# love_compass.net
KiCad netlist of a schematic drawn in EasyEDA Pro
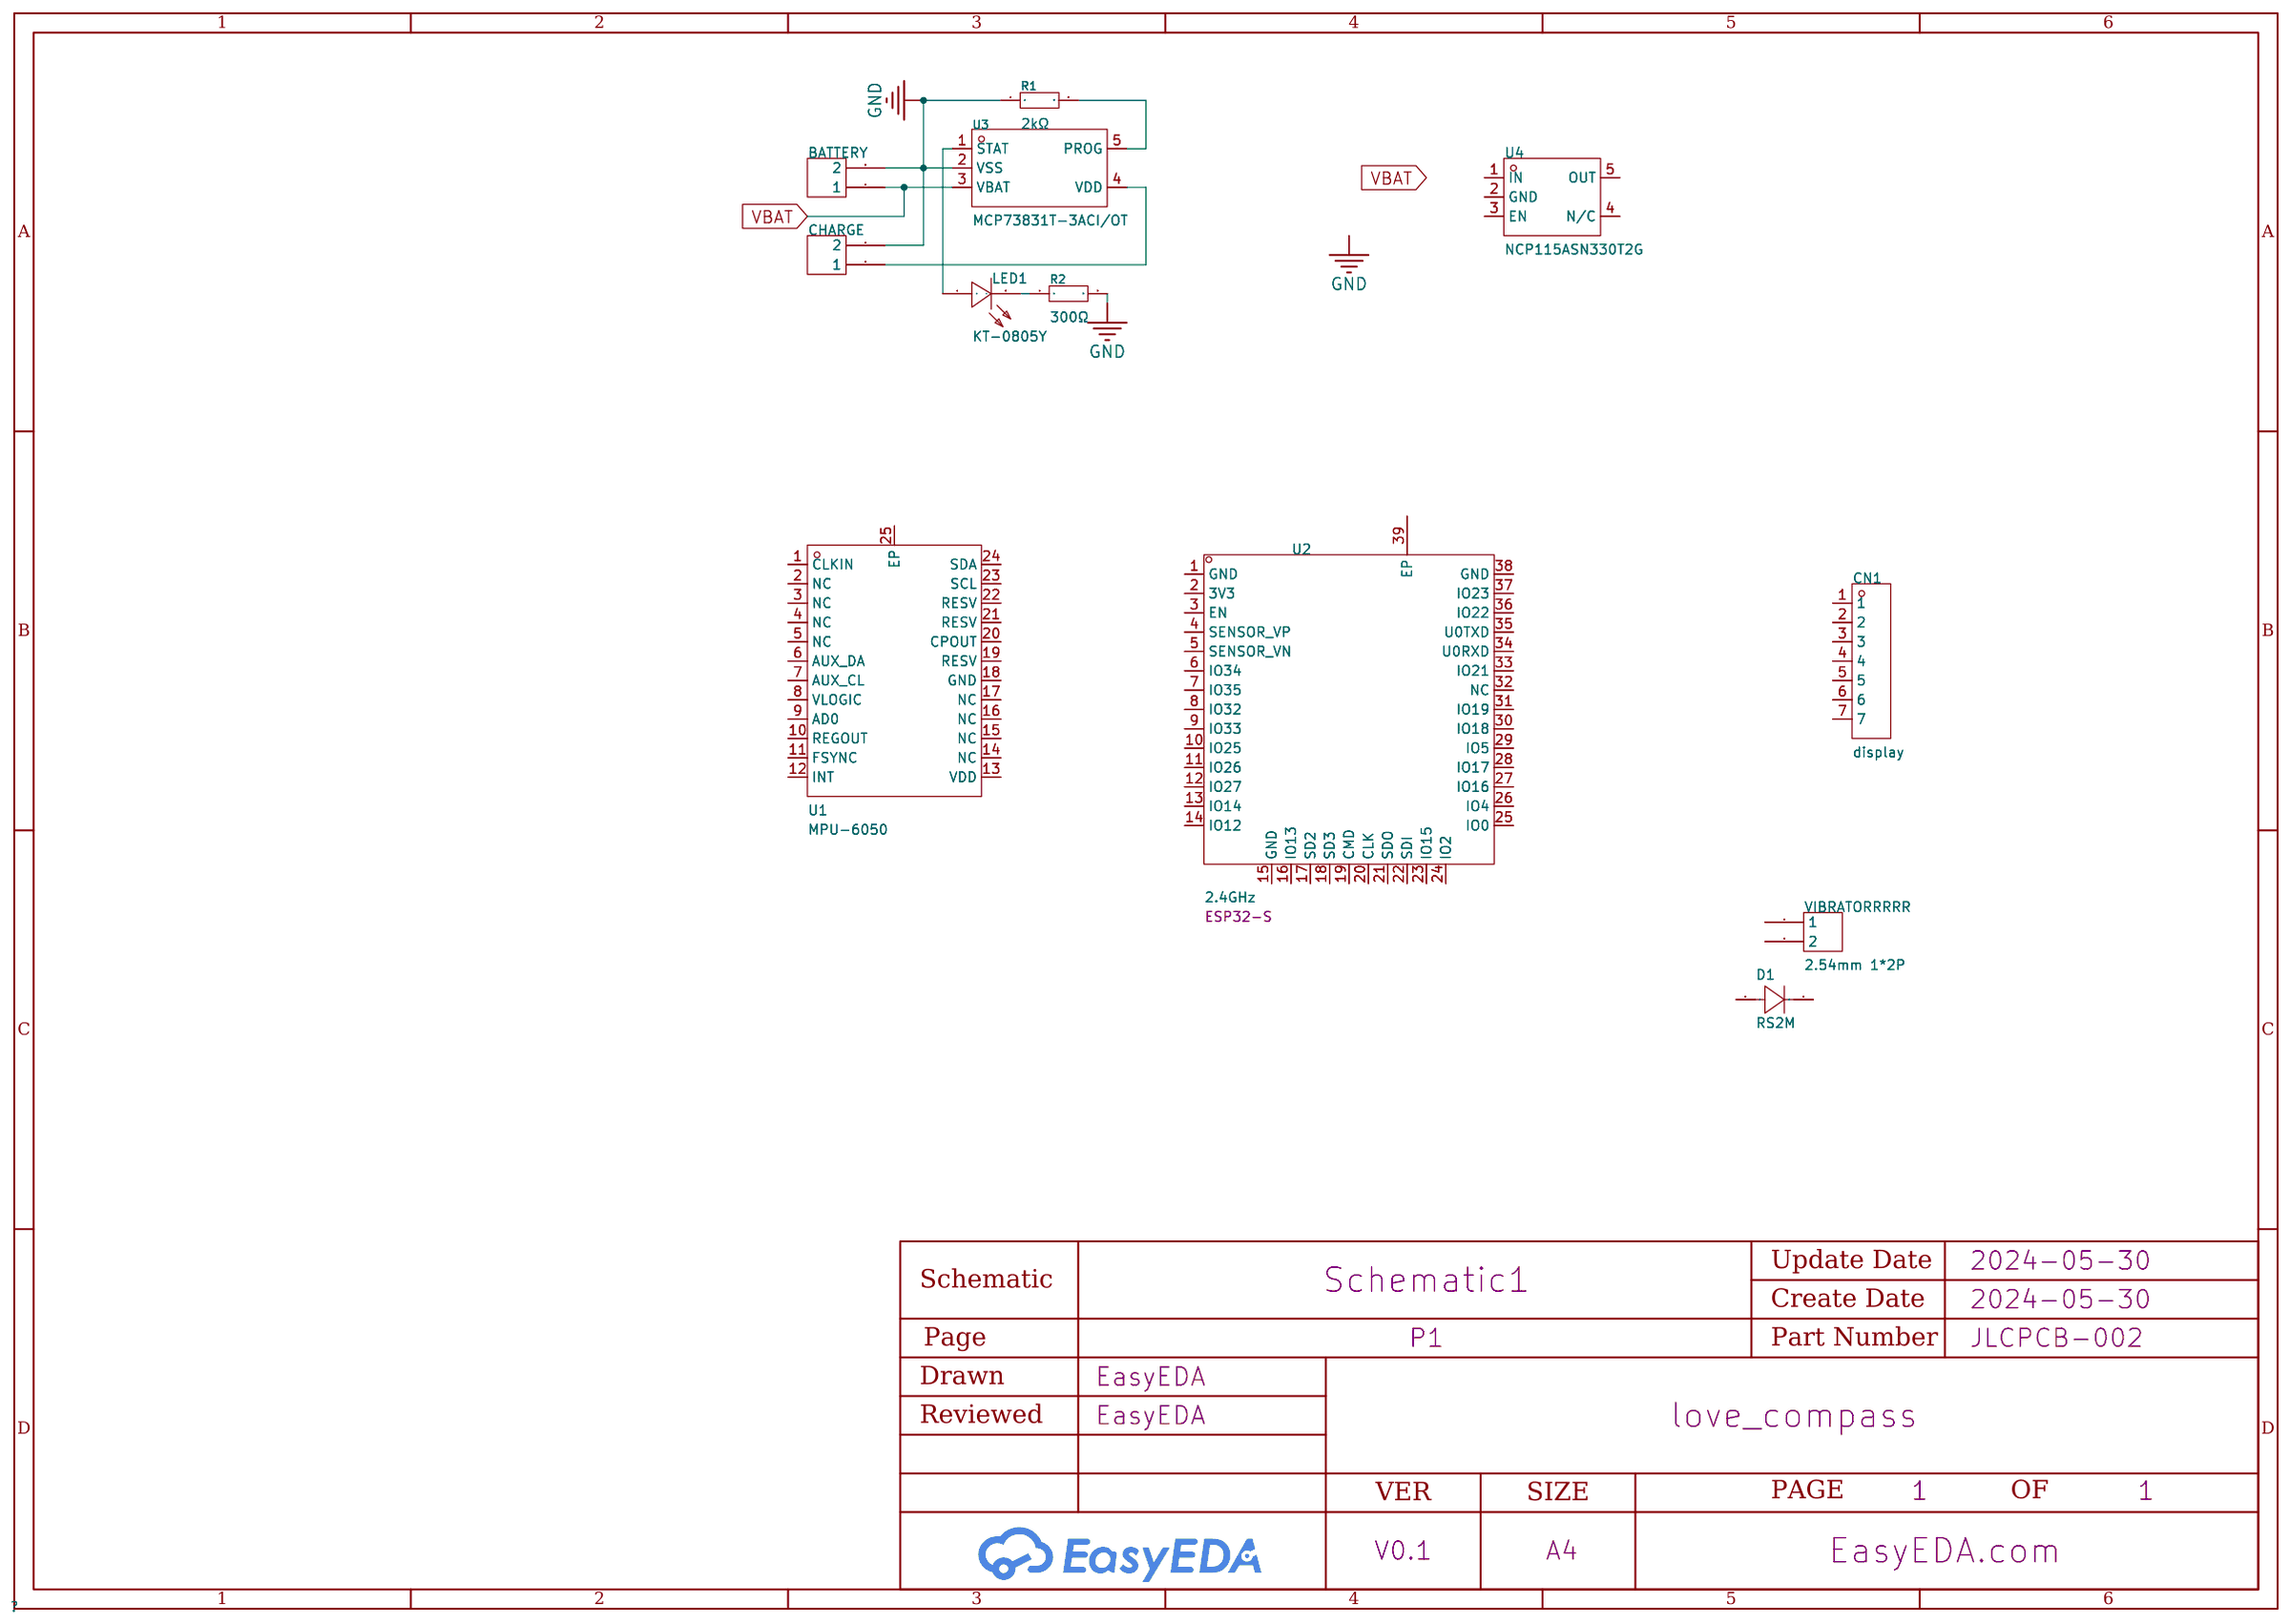
[diagram p0: schematic sheet]

(export (version "E")
  (design (tool "Eeschema 10.0.6"))
  (components
    (comp (ref "BATTERY")
      (value "2.54mm 1*2P")
      (footprint "easyedapro:HDR-TH_2P-P2.54-V-M")
      (libsource (lib "easyedapro") (part "2.54mm 1*2P"))
    )
    (comp (ref "CHARGE")
      (value "2.54mm 1*2P")
      (footprint "easyedapro:HDR-TH_2P-P2.54-V-M")
      (libsource (lib "easyedapro") (part "2.54mm 1*2P"))
    )
    (comp (ref "CN1")
      (value "display")
      (footprint "easyedapro:CONN-TH_7P-P2.54_C9900012194")
      (libsource (lib "easyedapro") (part "1*7PIN排间距2.54MM"))
    )
    (comp (ref "D1")
      (value "RS2M")
      (footprint "easyedapro:SMA-SMD_L4.4-W2.7-LS5.4-RD")
      (fields (field (name "Manufacturer") "HXY MOSFET(华轩阳电子)"))
      (libsource (lib "easyedapro") (part "RS2M_C5199100"))
    )
    (comp (ref "LED1")
      (value "KT-0805Y")
      (footprint "easyedapro:LED0805-R-RD")
      (fields (field (name "Manufacturer") "KENTO"))
      (libsource (lib "easyedapro") (part "17-21SUYC/TR8"))
    )
    (comp (ref "R1")
      (value "2kΩ")
      (footprint "easyedapro:R0805")
      (fields
        (field (name "Manufacturer Part") "0805W8F2001T5E")
        (field (name "Manufacturer") "UNI-ROYAL(厚声)")
      )
      (libsource (lib "easyedapro") (part "0805W8F2001T5E"))
    )
    (comp (ref "R2")
      (value "300Ω")
      (footprint "easyedapro:R0805")
      (fields
        (field (name "Manufacturer Part") "0805W8F3000T5E")
        (field (name "Manufacturer") "UNI-ROYAL(厚声)")
      )
      (libsource (lib "easyedapro") (part "0805W8F3000T5E"))
    )
    (comp (ref "U1")
      (value "MPU-6050")
      (footprint "easyedapro:QFN-24_L4.0-W4.0-P0.50-BL-EP2.7")
      (description "Sensor Type:加速度计陀螺仪 Operating Temperature:-40°C~+85°C Operating Temperature:-40°C~+85°C")
      (fields (field (name "Manufacturer") "TDK InvenSense(应美盛)"))
      (libsource (lib "easyedapro") (part "MPU-6050_C24112"))
    )
    (comp (ref "U2")
      (value "2.4GHz")
      (footprint "easyedapro:WIRELM-SMD_ESP32-S")
      (fields (field (name "Manufacturer Part") "ESP32-S") (field (name "Manufacturer") "Ai-Thinker(安信可)"))
      (libsource (lib "easyedapro") (part "ESP32-S"))
    )
    (comp (ref "U3")
      (value "MCP73831T-3ACI/OT")
      (footprint "easyedapro:SOT-23-5_L2.9-W1.6-P0.95-LS2.8-BR")
      (fields (field (name "Manufacturer") "MICROCHIP(美国微芯)"))
      (libsource (lib "easyedapro") (part "MCP73831T-3ACI/OT"))
    )
    (comp (ref "U4")
      (value "NCP115ASN330T2G")
      (footprint "easyedapro:SOT-23-5_L3.0-W1.7-P0.95-LS2.8-BL")
      (fields (field (name "Manufacturer") "onsemi(安森美)"))
      (libsource (lib "easyedapro") (part "NCP115ASN330T2G"))
    )
    (comp (ref "VIBRATORRRRR")
      (value "2.54mm 1*2P")
      (footprint "easyedapro:HDR-TH_2P-P2.54-V-M")
      (libsource (lib "easyedapro") (part "2.54mm 1*2P"))
    )
  )
  (nets
    (net (code "1") (name "GND") (class "Default")
      (node (ref "BATTERY") (pin "2") (pinfunction "2_2") (pintype "input"))
      (node (ref "CHARGE") (pin "2") (pinfunction "2_2") (pintype "input"))
      (node (ref "R1") (pin "1") (pinfunction "1_1") (pintype "input"))
      (node (ref "R2") (pin "2") (pinfunction "2_2") (pintype "input"))
      (node (ref "U3") (pin "2") (pinfunction "VSS_2") (pintype "input"))
    )
    (net (code "2") (name "Net-(LED1-+)") (class "Default")
      (node (ref "LED1") (pin "1") (pinfunction "+_1") (pintype "unspecified"))
      (node (ref "U3") (pin "1") (pinfunction "STAT_1") (pintype "input"))
    )
    (net (code "3") (name "Net-(LED1--)") (class "Default")
      (node (ref "LED1") (pin "2") (pinfunction "-_2") (pintype "unspecified"))
      (node (ref "R2") (pin "1") (pinfunction "1_1") (pintype "input"))
    )
    (net (code "4") (name "Net-(U3-PROG)") (class "Default")
      (node (ref "R1") (pin "2") (pinfunction "2_2") (pintype "input"))
      (node (ref "U3") (pin "5") (pinfunction "PROG_5") (pintype "input"))
    )
    (net (code "5") (name "Net-(U3-VDD)") (class "Default")
      (node (ref "CHARGE") (pin "1") (pinfunction "1_1") (pintype "input"))
      (node (ref "U3") (pin "4") (pinfunction "VDD_4") (pintype "input"))
    )
    (net (code "6") (name "VBAT") (class "Default")
      (node (ref "BATTERY") (pin "1") (pinfunction "1_1") (pintype "input"))
      (node (ref "U3") (pin "3") (pinfunction "VBAT_3") (pintype "input"))
    )
    (net (code "7") (name "unconnected-(CN1-Pad1)") (class "Default")
      (node (ref "CN1") (pin "1") (pinfunction "1_1") (pintype "unspecified"))
    )
    (net (code "8") (name "unconnected-(CN1-Pad2)") (class "Default")
      (node (ref "CN1") (pin "2") (pinfunction "2_2") (pintype "unspecified"))
    )
    (net (code "9") (name "unconnected-(CN1-Pad3)") (class "Default")
      (node (ref "CN1") (pin "3") (pinfunction "3_3") (pintype "unspecified"))
    )
    (net (code "10") (name "unconnected-(CN1-Pad4)") (class "Default")
      (node (ref "CN1") (pin "4") (pinfunction "4_4") (pintype "unspecified"))
    )
    (net (code "11") (name "unconnected-(CN1-Pad5)") (class "Default")
      (node (ref "CN1") (pin "5") (pinfunction "5_5") (pintype "unspecified"))
    )
    (net (code "12") (name "unconnected-(CN1-Pad6)") (class "Default")
      (node (ref "CN1") (pin "6") (pinfunction "6_6") (pintype "unspecified"))
    )
    (net (code "13") (name "unconnected-(CN1-Pad7)") (class "Default")
      (node (ref "CN1") (pin "7") (pinfunction "7_7") (pintype "unspecified"))
    )
    (net (code "14") (name "unconnected-(D1-A-Pad2)") (class "Default")
      (node (ref "D1") (pin "2") (pinfunction "A_2") (pintype "unspecified"))
    )
    (net (code "15") (name "unconnected-(D1-K-Pad1)") (class "Default")
      (node (ref "D1") (pin "1") (pinfunction "K_1") (pintype "unspecified"))
    )
    (net (code "16") (name "unconnected-(U1-AD0-Pad9)") (class "Default")
      (node (ref "U1") (pin "9") (pinfunction "AD0_9") (pintype "unspecified"))
    )
    (net (code "17") (name "unconnected-(U1-AUX_CL-Pad7)") (class "Default")
      (node (ref "U1") (pin "7") (pinfunction "AUX_CL_7") (pintype "unspecified"))
    )
    (net (code "18") (name "unconnected-(U1-AUX_DA-Pad6)") (class "Default")
      (node (ref "U1") (pin "6") (pinfunction "AUX_DA_6") (pintype "unspecified"))
    )
    (net (code "19") (name "unconnected-(U1-CLKIN-Pad1)") (class "Default")
      (node (ref "U1") (pin "1") (pinfunction "CLKIN_1") (pintype "unspecified"))
    )
    (net (code "20") (name "unconnected-(U1-CPOUT-Pad20)") (class "Default")
      (node (ref "U1") (pin "20") (pinfunction "CPOUT_20") (pintype "unspecified"))
    )
    (net (code "21") (name "unconnected-(U1-EP-Pad25)") (class "Default")
      (node (ref "U1") (pin "25") (pinfunction "EP_25") (pintype "unspecified"))
    )
    (net (code "22") (name "unconnected-(U1-FSYNC-Pad11)") (class "Default")
      (node (ref "U1") (pin "11") (pinfunction "FSYNC_11") (pintype "unspecified"))
    )
    (net (code "23") (name "unconnected-(U1-GND-Pad18)") (class "Default")
      (node (ref "U1") (pin "18") (pinfunction "GND_18") (pintype "unspecified"))
    )
    (net (code "24") (name "unconnected-(U1-INT-Pad12)") (class "Default")
      (node (ref "U1") (pin "12") (pinfunction "INT_12") (pintype "unspecified"))
    )
    (net (code "25") (name "unconnected-(U1-NC-Pad2)") (class "Default")
      (node (ref "U1") (pin "2") (pinfunction "NC_2") (pintype "unspecified"))
    )
    (net (code "26") (name "unconnected-(U1-NC-Pad3)") (class "Default")
      (node (ref "U1") (pin "3") (pinfunction "NC_3") (pintype "unspecified"))
    )
    (net (code "27") (name "unconnected-(U1-NC-Pad4)") (class "Default")
      (node (ref "U1") (pin "4") (pinfunction "NC_4") (pintype "unspecified"))
    )
    (net (code "28") (name "unconnected-(U1-NC-Pad5)") (class "Default")
      (node (ref "U1") (pin "5") (pinfunction "NC_5") (pintype "unspecified"))
    )
    (net (code "29") (name "unconnected-(U1-NC-Pad14)") (class "Default")
      (node (ref "U1") (pin "14") (pinfunction "NC_14") (pintype "unspecified"))
    )
    (net (code "30") (name "unconnected-(U1-NC-Pad15)") (class "Default")
      (node (ref "U1") (pin "15") (pinfunction "NC_15") (pintype "unspecified"))
    )
    (net (code "31") (name "unconnected-(U1-NC-Pad16)") (class "Default")
      (node (ref "U1") (pin "16") (pinfunction "NC_16") (pintype "unspecified"))
    )
    (net (code "32") (name "unconnected-(U1-NC-Pad17)") (class "Default")
      (node (ref "U1") (pin "17") (pinfunction "NC_17") (pintype "unspecified"))
    )
    (net (code "33") (name "unconnected-(U1-REGOUT-Pad10)") (class "Default")
      (node (ref "U1") (pin "10") (pinfunction "REGOUT_10") (pintype "unspecified"))
    )
    (net (code "34") (name "unconnected-(U1-RESV-Pad19)") (class "Default")
      (node (ref "U1") (pin "19") (pinfunction "RESV_19") (pintype "unspecified"))
    )
    (net (code "35") (name "unconnected-(U1-RESV-Pad21)") (class "Default")
      (node (ref "U1") (pin "21") (pinfunction "RESV_21") (pintype "unspecified"))
    )
    (net (code "36") (name "unconnected-(U1-RESV-Pad22)") (class "Default")
      (node (ref "U1") (pin "22") (pinfunction "RESV_22") (pintype "unspecified"))
    )
    (net (code "37") (name "unconnected-(U1-SCL-Pad23)") (class "Default")
      (node (ref "U1") (pin "23") (pinfunction "SCL_23") (pintype "unspecified"))
    )
    (net (code "38") (name "unconnected-(U1-SDA-Pad24)") (class "Default")
      (node (ref "U1") (pin "24") (pinfunction "SDA_24") (pintype "unspecified"))
    )
    (net (code "39") (name "unconnected-(U1-VDD-Pad13)") (class "Default")
      (node (ref "U1") (pin "13") (pinfunction "VDD_13") (pintype "unspecified"))
    )
    (net (code "40") (name "unconnected-(U1-VLOGIC-Pad8)") (class "Default")
      (node (ref "U1") (pin "8") (pinfunction "VLOGIC_8") (pintype "unspecified"))
    )
    (net (code "41") (name "unconnected-(U2-3V3-Pad2)") (class "Default")
      (node (ref "U2") (pin "2") (pinfunction "3V3_2") (pintype "input"))
    )
    (net (code "42") (name "unconnected-(U2-CLK-Pad20)") (class "Default")
      (node (ref "U2") (pin "20") (pinfunction "CLK_20") (pintype "input"))
    )
    (net (code "43") (name "unconnected-(U2-CMD-Pad19)") (class "Default")
      (node (ref "U2") (pin "19") (pinfunction "CMD_19") (pintype "input"))
    )
    (net (code "44") (name "unconnected-(U2-EN-Pad3)") (class "Default")
      (node (ref "U2") (pin "3") (pinfunction "EN_3") (pintype "input"))
    )
    (net (code "45") (name "unconnected-(U2-EP-Pad39)") (class "Default")
      (node (ref "U2") (pin "39") (pinfunction "EP_39") (pintype "input"))
    )
    (net (code "46") (name "unconnected-(U2-GND-Pad1)") (class "Default")
      (node (ref "U2") (pin "1") (pinfunction "GND_1") (pintype "input"))
    )
    (net (code "47") (name "unconnected-(U2-GND-Pad15)") (class "Default")
      (node (ref "U2") (pin "15") (pinfunction "GND_15") (pintype "input"))
    )
    (net (code "48") (name "unconnected-(U2-GND-Pad38)") (class "Default")
      (node (ref "U2") (pin "38") (pinfunction "GND_38") (pintype "input"))
    )
    (net (code "49") (name "unconnected-(U2-IO0-Pad25)") (class "Default")
      (node (ref "U2") (pin "25") (pinfunction "IO0_25") (pintype "input"))
    )
    (net (code "50") (name "unconnected-(U2-IO2-Pad24)") (class "Default")
      (node (ref "U2") (pin "24") (pinfunction "IO2_24") (pintype "input"))
    )
    (net (code "51") (name "unconnected-(U2-IO4-Pad26)") (class "Default")
      (node (ref "U2") (pin "26") (pinfunction "IO4_26") (pintype "input"))
    )
    (net (code "52") (name "unconnected-(U2-IO5-Pad29)") (class "Default")
      (node (ref "U2") (pin "29") (pinfunction "IO5_29") (pintype "input"))
    )
    (net (code "53") (name "unconnected-(U2-IO12-Pad14)") (class "Default")
      (node (ref "U2") (pin "14") (pinfunction "IO12_14") (pintype "input"))
    )
    (net (code "54") (name "unconnected-(U2-IO13-Pad16)") (class "Default")
      (node (ref "U2") (pin "16") (pinfunction "IO13_16") (pintype "input"))
    )
    (net (code "55") (name "unconnected-(U2-IO14-Pad13)") (class "Default")
      (node (ref "U2") (pin "13") (pinfunction "IO14_13") (pintype "input"))
    )
    (net (code "56") (name "unconnected-(U2-IO15-Pad23)") (class "Default")
      (node (ref "U2") (pin "23") (pinfunction "IO15_23") (pintype "input"))
    )
    (net (code "57") (name "unconnected-(U2-IO16-Pad27)") (class "Default")
      (node (ref "U2") (pin "27") (pinfunction "IO16_27") (pintype "input"))
    )
    (net (code "58") (name "unconnected-(U2-IO17-Pad28)") (class "Default")
      (node (ref "U2") (pin "28") (pinfunction "IO17_28") (pintype "input"))
    )
    (net (code "59") (name "unconnected-(U2-IO18-Pad30)") (class "Default")
      (node (ref "U2") (pin "30") (pinfunction "IO18_30") (pintype "input"))
    )
    (net (code "60") (name "unconnected-(U2-IO19-Pad31)") (class "Default")
      (node (ref "U2") (pin "31") (pinfunction "IO19_31") (pintype "input"))
    )
    (net (code "61") (name "unconnected-(U2-IO21-Pad33)") (class "Default")
      (node (ref "U2") (pin "33") (pinfunction "IO21_33") (pintype "input"))
    )
    (net (code "62") (name "unconnected-(U2-IO22-Pad36)") (class "Default")
      (node (ref "U2") (pin "36") (pinfunction "IO22_36") (pintype "input"))
    )
    (net (code "63") (name "unconnected-(U2-IO23-Pad37)") (class "Default")
      (node (ref "U2") (pin "37") (pinfunction "IO23_37") (pintype "input"))
    )
    (net (code "64") (name "unconnected-(U2-IO25-Pad10)") (class "Default")
      (node (ref "U2") (pin "10") (pinfunction "IO25_10") (pintype "input"))
    )
    (net (code "65") (name "unconnected-(U2-IO26-Pad11)") (class "Default")
      (node (ref "U2") (pin "11") (pinfunction "IO26_11") (pintype "input"))
    )
    (net (code "66") (name "unconnected-(U2-IO27-Pad12)") (class "Default")
      (node (ref "U2") (pin "12") (pinfunction "IO27_12") (pintype "input"))
    )
    (net (code "67") (name "unconnected-(U2-IO32-Pad8)") (class "Default")
      (node (ref "U2") (pin "8") (pinfunction "IO32_8") (pintype "input"))
    )
    (net (code "68") (name "unconnected-(U2-IO33-Pad9)") (class "Default")
      (node (ref "U2") (pin "9") (pinfunction "IO33_9") (pintype "input"))
    )
    (net (code "69") (name "unconnected-(U2-IO34-Pad6)") (class "Default")
      (node (ref "U2") (pin "6") (pinfunction "IO34_6") (pintype "input"))
    )
    (net (code "70") (name "unconnected-(U2-IO35-Pad7)") (class "Default")
      (node (ref "U2") (pin "7") (pinfunction "IO35_7") (pintype "input"))
    )
    (net (code "71") (name "unconnected-(U2-NC-Pad32)") (class "Default")
      (node (ref "U2") (pin "32") (pinfunction "NC_32") (pintype "input"))
    )
    (net (code "72") (name "unconnected-(U2-SD2-Pad17)") (class "Default")
      (node (ref "U2") (pin "17") (pinfunction "SD2_17") (pintype "input"))
    )
    (net (code "73") (name "unconnected-(U2-SD3-Pad18)") (class "Default")
      (node (ref "U2") (pin "18") (pinfunction "SD3_18") (pintype "input"))
    )
    (net (code "74") (name "unconnected-(U2-SDI-Pad22)") (class "Default")
      (node (ref "U2") (pin "22") (pinfunction "SDI_22") (pintype "input"))
    )
    (net (code "75") (name "unconnected-(U2-SDO-Pad21)") (class "Default")
      (node (ref "U2") (pin "21") (pinfunction "SDO_21") (pintype "input"))
    )
    (net (code "76") (name "unconnected-(U2-SENSOR_VN-Pad5)") (class "Default")
      (node (ref "U2") (pin "5") (pinfunction "SENSOR_VN_5") (pintype "input"))
    )
    (net (code "77") (name "unconnected-(U2-SENSOR_VP-Pad4)") (class "Default")
      (node (ref "U2") (pin "4") (pinfunction "SENSOR_VP_4") (pintype "input"))
    )
    (net (code "78") (name "unconnected-(U2-U0RXD-Pad34)") (class "Default")
      (node (ref "U2") (pin "34") (pinfunction "U0RXD_34") (pintype "input"))
    )
    (net (code "79") (name "unconnected-(U2-U0TXD-Pad35)") (class "Default")
      (node (ref "U2") (pin "35") (pinfunction "U0TXD_35") (pintype "input"))
    )
    (net (code "80") (name "unconnected-(U4-EN-Pad3)") (class "Default")
      (node (ref "U4") (pin "3") (pinfunction "EN_3") (pintype "input"))
    )
    (net (code "81") (name "unconnected-(U4-GND-Pad2)") (class "Default")
      (node (ref "U4") (pin "2") (pinfunction "GND_2") (pintype "input"))
    )
    (net (code "82") (name "unconnected-(U4-IN-Pad1)") (class "Default")
      (node (ref "U4") (pin "1") (pinfunction "IN_1") (pintype "input"))
    )
    (net (code "83") (name "unconnected-(U4-N{slash}C-Pad4)") (class "Default")
      (node (ref "U4") (pin "4") (pinfunction "N/C_4") (pintype "input"))
    )
    (net (code "84") (name "unconnected-(U4-OUT-Pad5)") (class "Default")
      (node (ref "U4") (pin "5") (pinfunction "OUT_5") (pintype "input"))
    )
    (net (code "85") (name "unconnected-(VIBRATORRRRR-Pad1)") (class "Default")
      (node (ref "VIBRATORRRRR") (pin "1") (pinfunction "1_1") (pintype "input"))
    )
    (net (code "86") (name "unconnected-(VIBRATORRRRR-Pad2)") (class "Default")
      (node (ref "VIBRATORRRRR") (pin "2") (pinfunction "2_2") (pintype "input"))
    )
  )
)
